# Power.net
KiCad netlist of a schematic drawn in Altium Designer
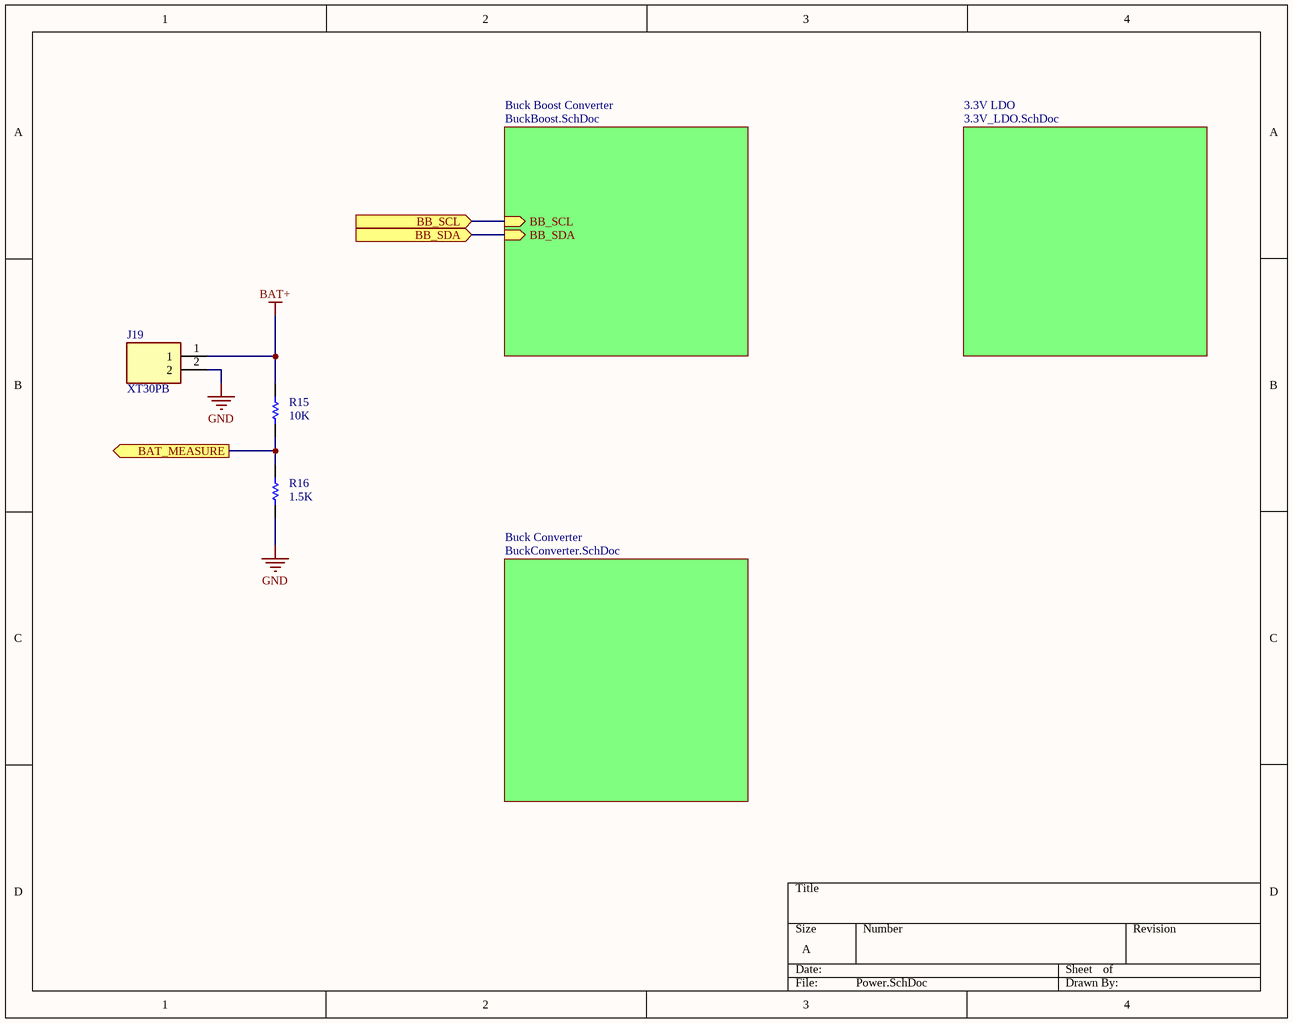
[diagram p0: Power.SchDoc]

(export (version "E")
  (design (tool "Eeschema 10.0.6"))
  (components
    (comp (ref "J19")
      (value "XT30PB")
      (footprint "SamacSys:XT30PB")
      (description "Connector")
      (libsource (lib "SamacSys") (part "XT30PB"))
    )
    (comp (ref "R15")
      (value "RC0402FR-0710KL")
      (footprint "RESC1005X40X25LL05T10")
      (fields (field (name "MANUFACTURER") "Yageo / Phycomp") (field (name "RESISTANCE") "10K"))
      (libsource (lib "Altium Content Vault") (part "RES"))
    )
    (comp (ref "R16")
      (value "RC0402FR-071K5L")
      (footprint "RESC1005X40X25ML05T10")
      (fields (field (name "MANUFACTURER") "Yageo / Phycomp") (field (name "RESISTANCE") "1.5K"))
      (libsource (lib "Altium Content Vault") (part "RES"))
    )
  )
  (nets
    (net (code "1") (name "/BAT_MEASURE") (class "Default")
      (node (ref "R15") (pin "1") (pinfunction "1_1") (pintype "passive"))
      (node (ref "R16") (pin "2") (pinfunction "2_2") (pintype "passive"))
    )
    (net (code "4") (name "BAT+") (class "Default")
      (node (ref "J19") (pin "1") (pinfunction "1_1") (pintype "passive"))
      (node (ref "R15") (pin "2") (pinfunction "2_2") (pintype "passive"))
    )
    (net (code "5") (name "GND") (class "Default")
      (node (ref "J19") (pin "2") (pinfunction "2_2") (pintype "passive"))
      (node (ref "R16") (pin "1") (pinfunction "1_1") (pintype "passive"))
    )
  )
)
